# 0002.net
KiCad netlist of a schematic drawn in EasyEDA
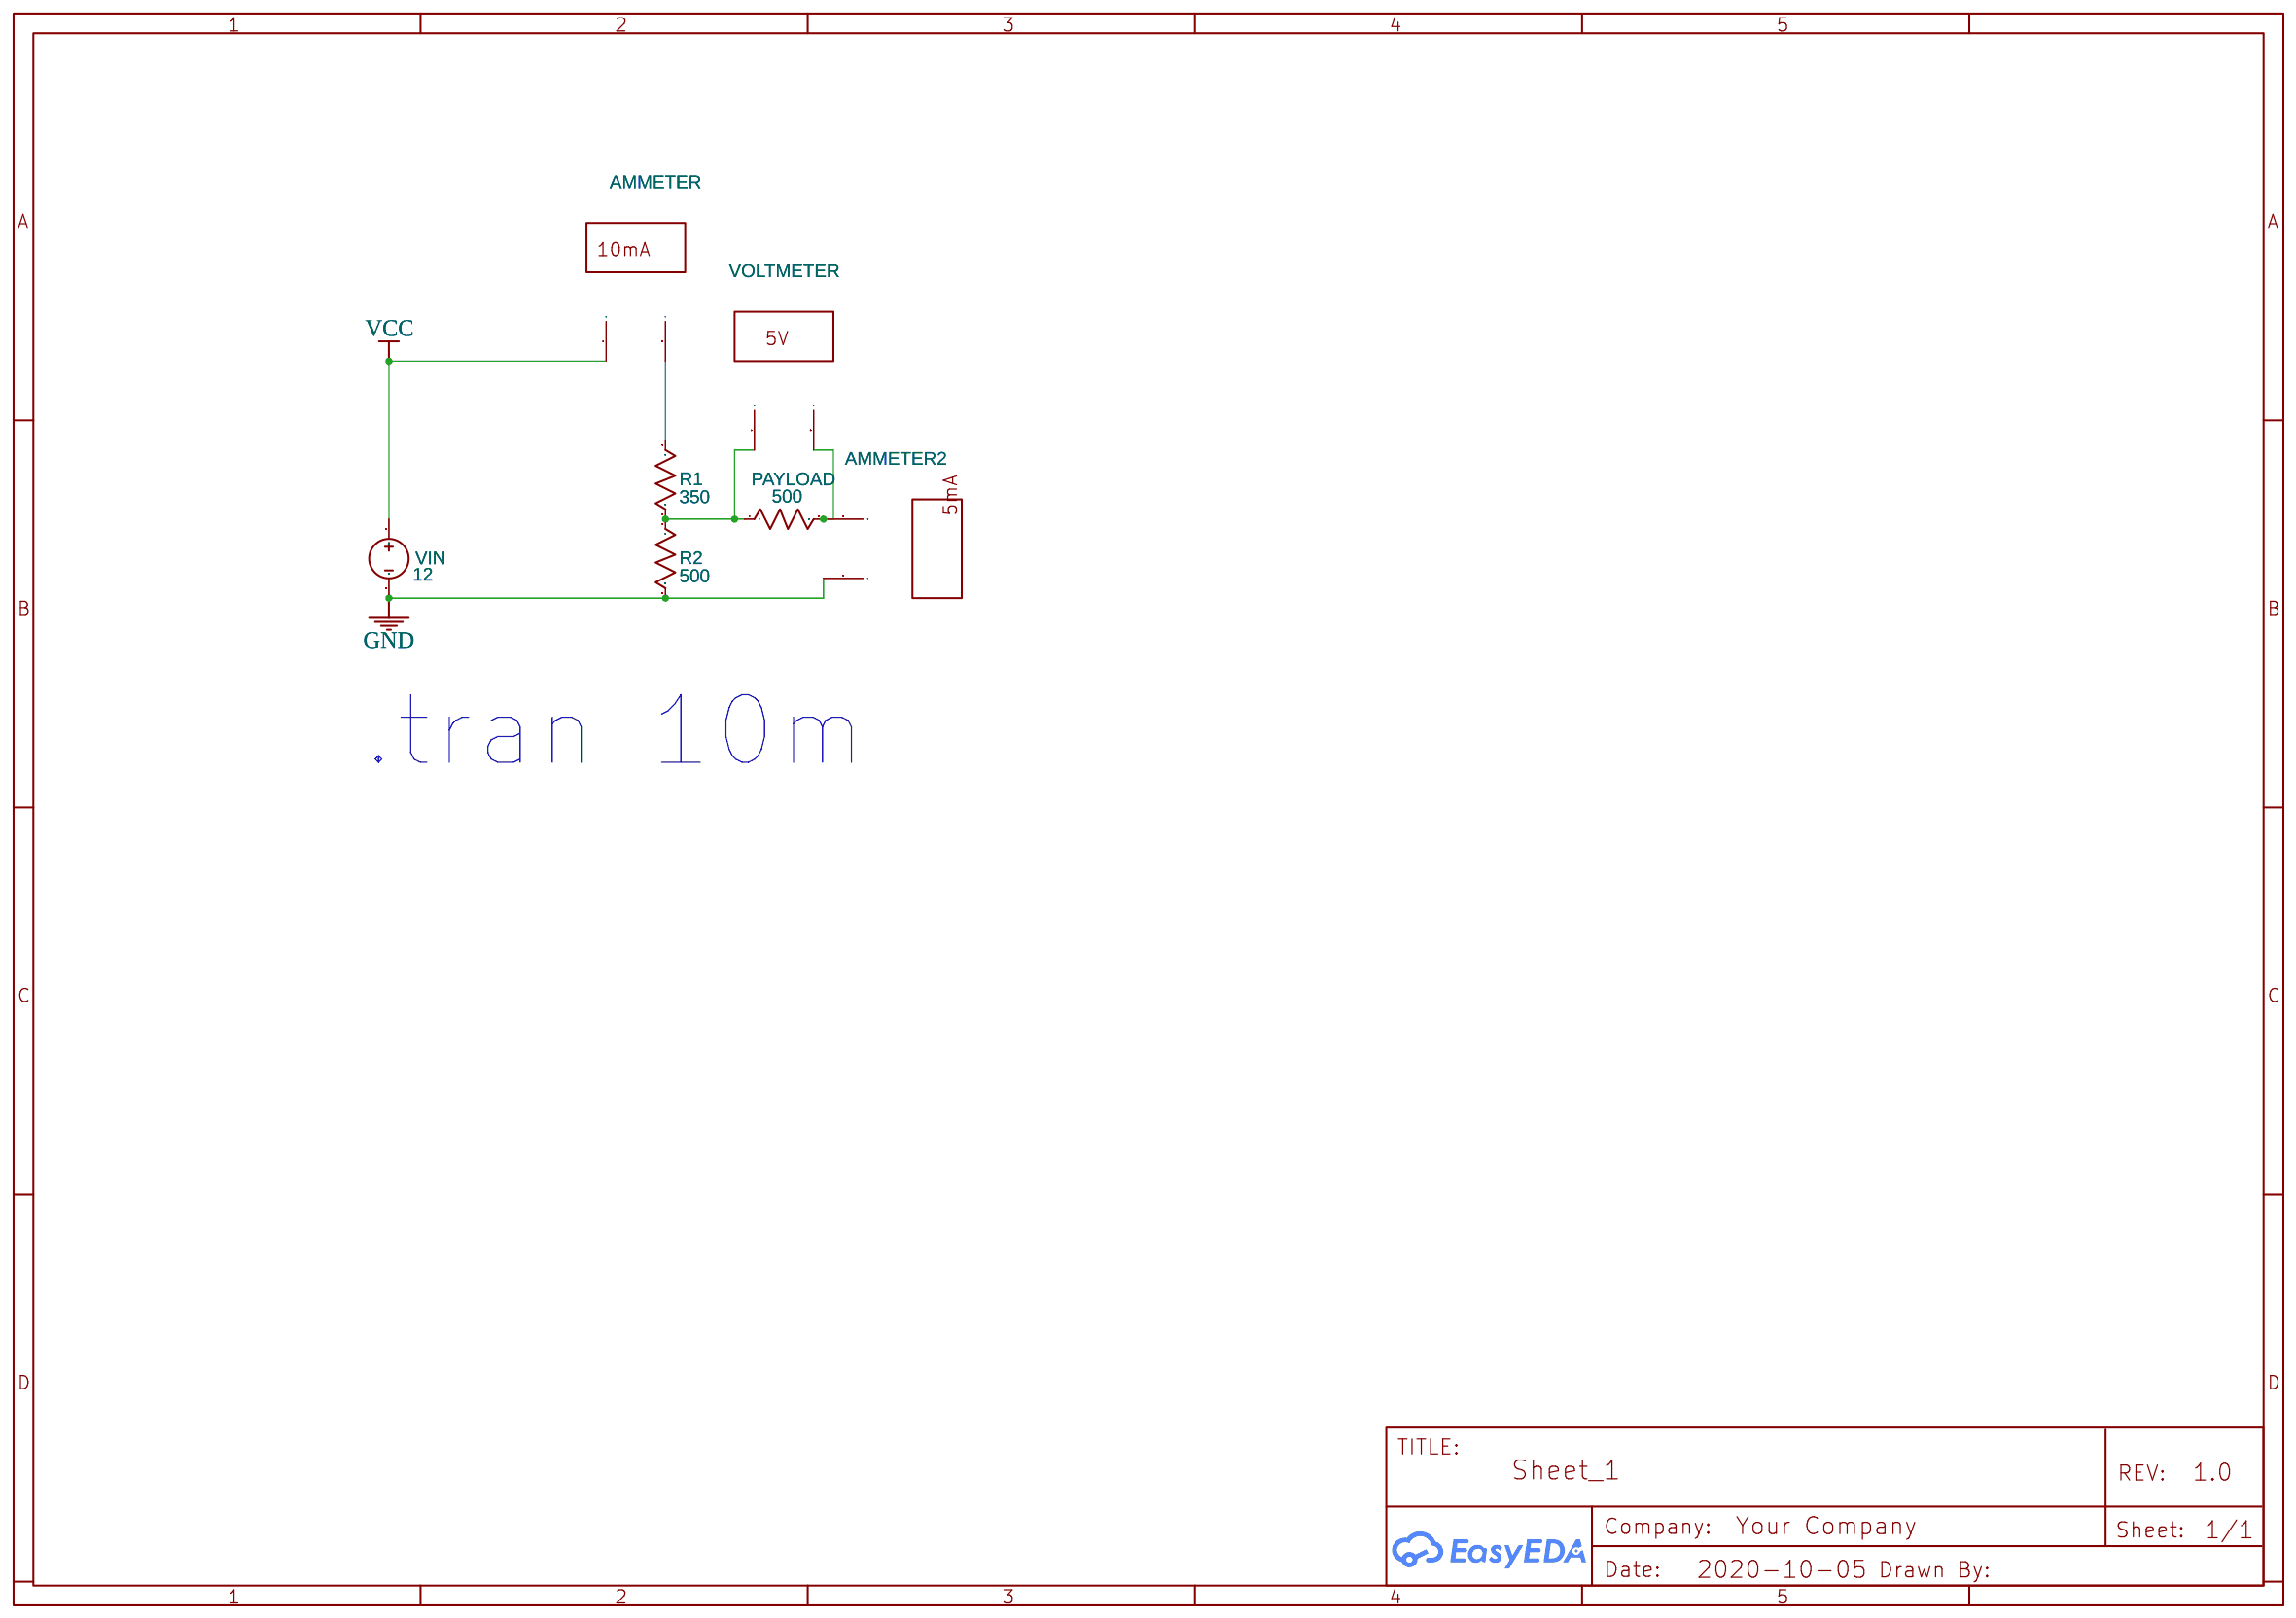
[diagram p0: schematic sheet]

(export (version "E")
  (design (tool "Eeschema 10.0.6"))
  (components
    (comp (ref "AMMETER") (value "Multimeter") (libsource (lib "") (part "MULTIMETER_1")))
    (comp (ref "AMMETER2") (value "Multimeter") (libsource (lib "") (part "MULTIMETER")))
    (comp (ref "PAYLOAD") (value "500") (libsource (lib "") (part "Resistor_US_1")))
    (comp (ref "R1") (value "350") (libsource (lib "") (part "Resistor_US")))
    (comp (ref "R2") (value "500") (libsource (lib "") (part "Resistor_US")))
    (comp (ref "VIN") (value "12") (libsource (lib "") (part "VDC")))
    (comp (ref "VOLTMETER") (value "Multimeter") (libsource (lib "") (part "MULTIMETER_2")))
  )
  (nets
    (net (code "1") (name "GND") (class "Default")
      (node (ref "AMMETER2") (pin "2") (pinfunction "I_2") (pintype "unspecified"))
      (node (ref "R2") (pin "2") (pinfunction "2_2") (pintype "unspecified"))
      (node (ref "VIN") (pin "2") (pinfunction "2_2") (pintype "unspecified"))
    )
    (net (code "2") (name "Net-(AMMETER-I)") (class "Default")
      (node (ref "AMMETER") (pin "2") (pinfunction "I_2") (pintype "unspecified"))
      (node (ref "R1") (pin "1") (pinfunction "1_1") (pintype "unspecified"))
    )
    (net (code "3") (name "Net-(AMMETER2-+)") (class "Default")
      (node (ref "AMMETER2") (pin "1") (pinfunction "+_1") (pintype "unspecified"))
      (node (ref "PAYLOAD") (pin "2") (pinfunction "2_2") (pintype "unspecified"))
      (node (ref "VOLTMETER") (pin "2") (pinfunction "I_2") (pintype "unspecified"))
    )
    (net (code "4") (name "Net-(VOLTMETER-+)") (class "Default")
      (node (ref "PAYLOAD") (pin "1") (pinfunction "1_1") (pintype "unspecified"))
      (node (ref "R1") (pin "2") (pinfunction "2_2") (pintype "unspecified"))
      (node (ref "R2") (pin "1") (pinfunction "1_1") (pintype "unspecified"))
      (node (ref "VOLTMETER") (pin "1") (pinfunction "+_1") (pintype "unspecified"))
    )
    (net (code "5") (name "VCC") (class "Default")
      (node (ref "AMMETER") (pin "1") (pinfunction "+_1") (pintype "unspecified"))
      (node (ref "VIN") (pin "1") (pinfunction "1_1") (pintype "unspecified"))
    )
  )
)
